# 09_-USB_IMU_GNSS.net
KiCad netlist of a schematic drawn in Altium Designer
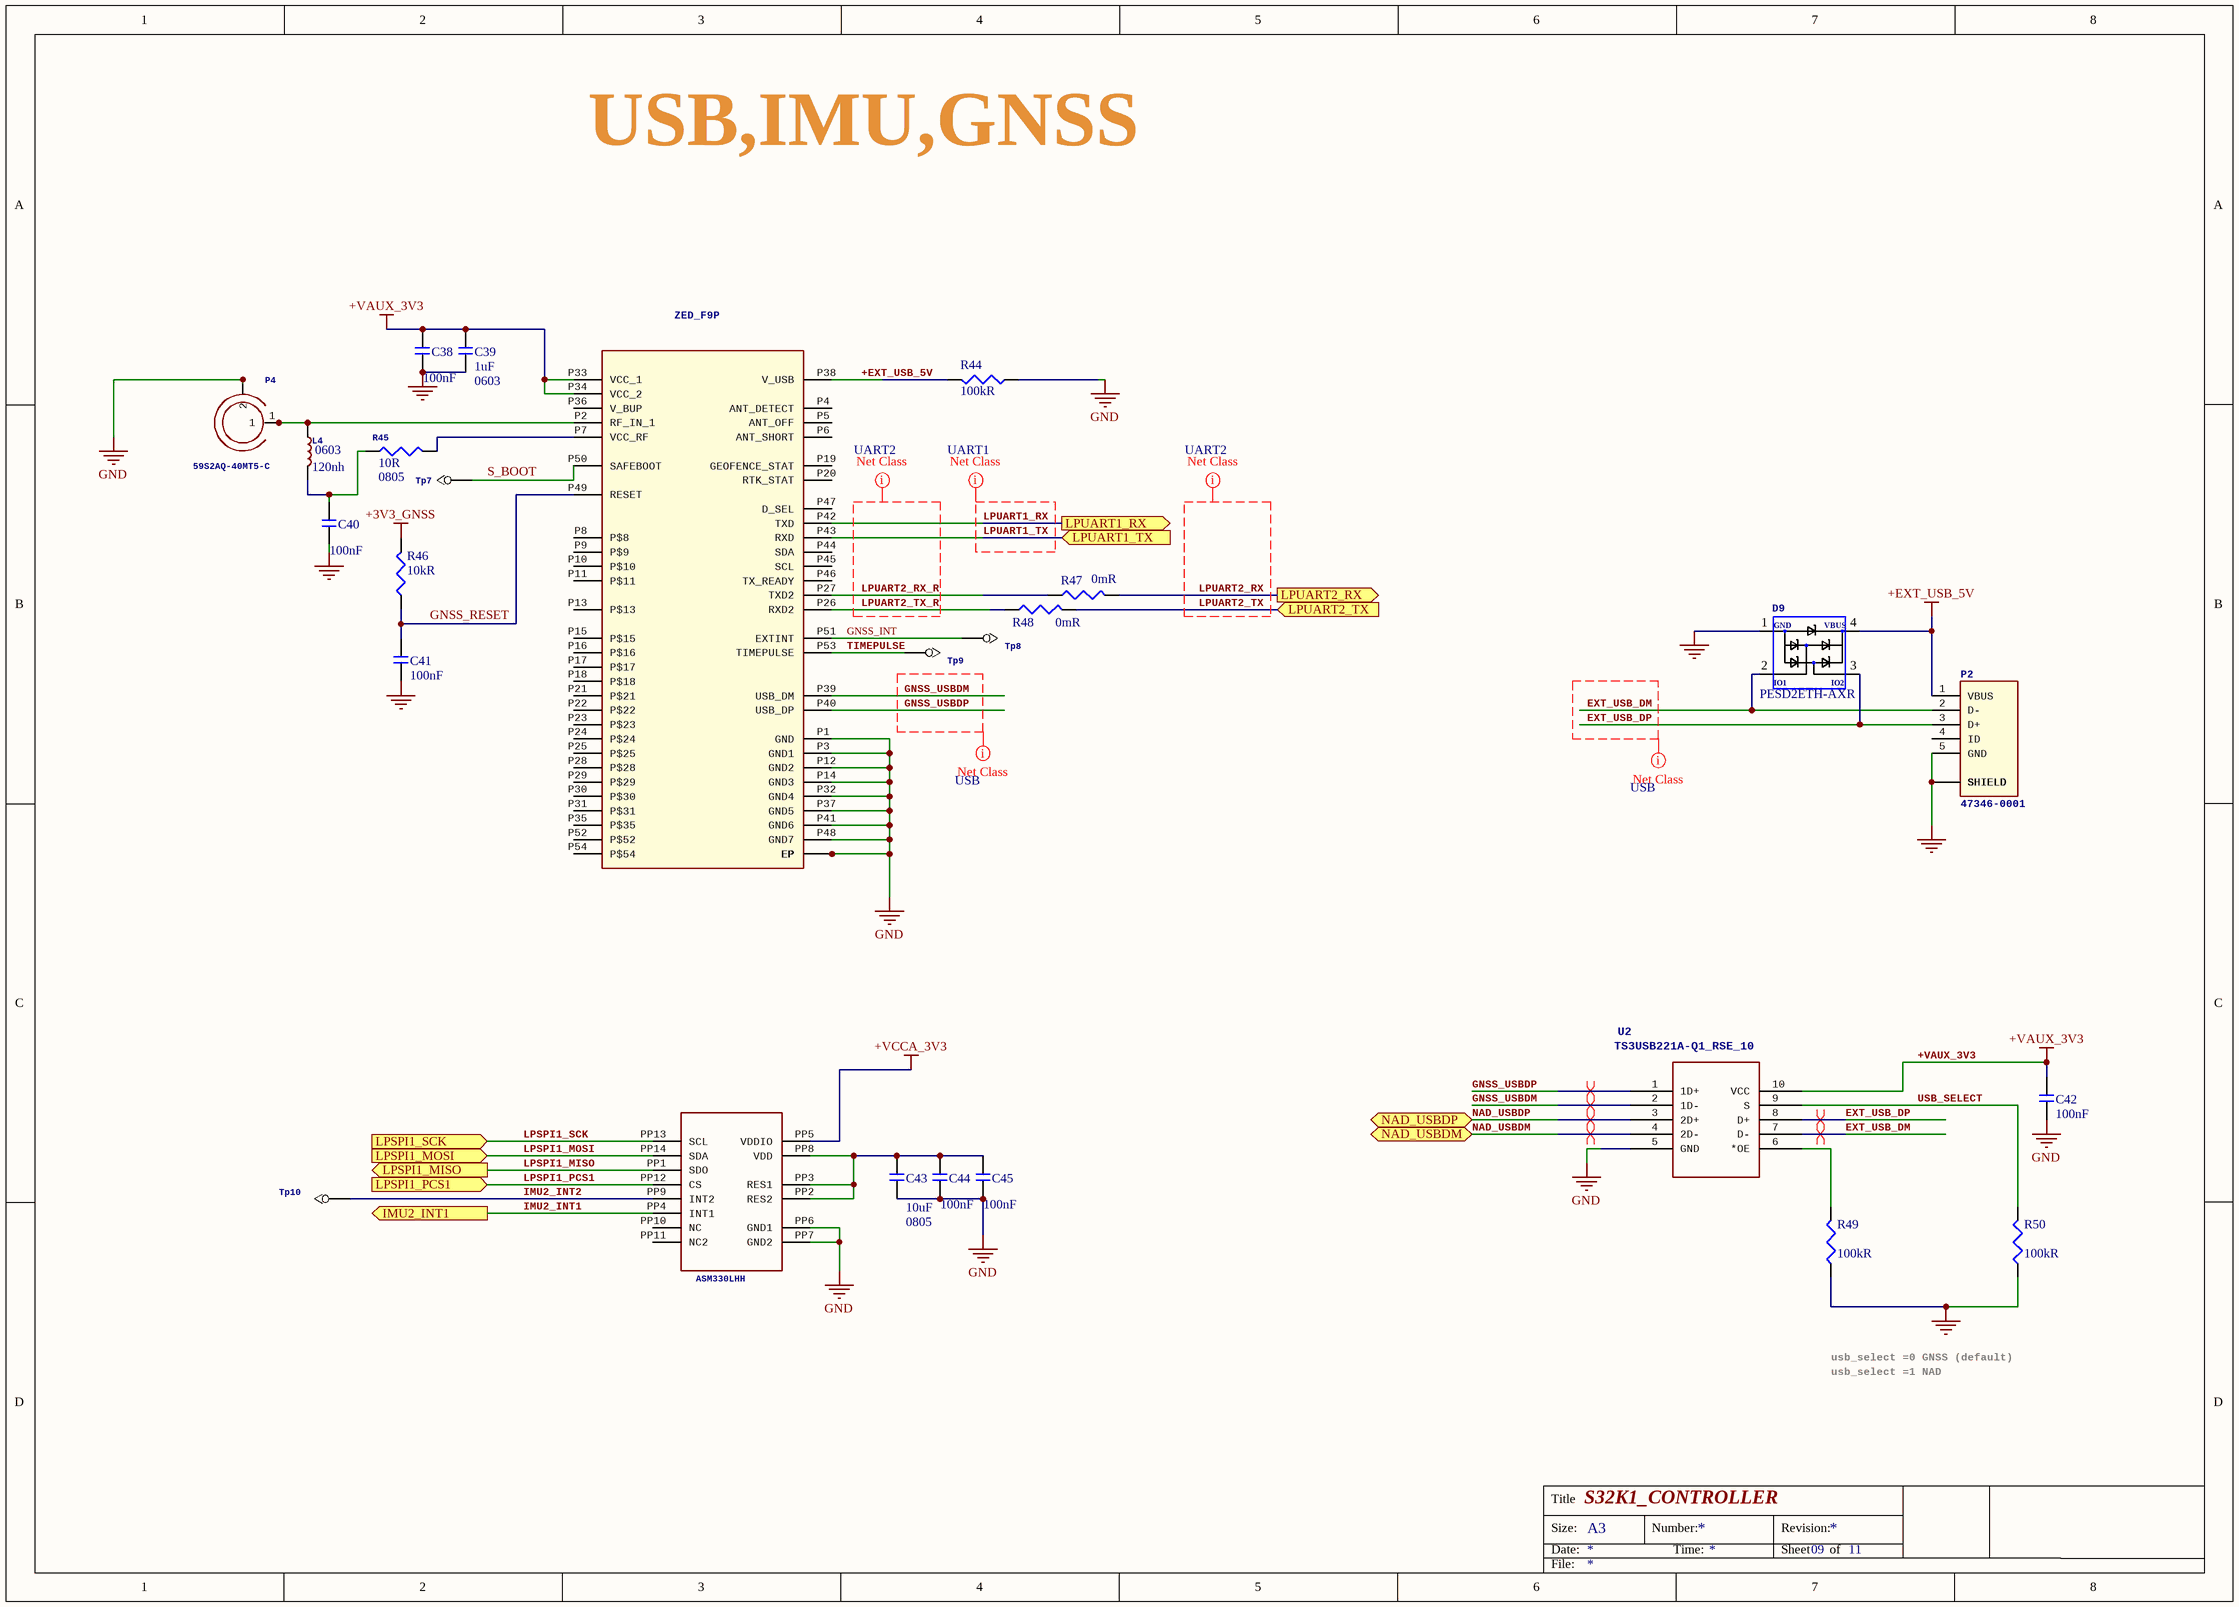
[diagram p0: [09]-USB,IMU,GNSS.SchDoc]

(export (version "E")
  (design (tool "Eeschema 10.0.6"))
  (components
    (comp (ref "C38")
      (value "GCM155R71C104KA55D")
      (footprint "CAP0402")
      (description "Multilayer Ceramic Capacitors (MLCC) - SMD/SMT 0402 0.1uF 16volts X7R 10%")
      (fields
        (field (name "MANUFACTURER") "Murata")
        (field (name "TOLERANCE") "10%")
        (field (name "CAPACITANCE") "100nF")
      )
      (libsource (lib "altium-import") (part "root_0_GCM155R71C104KA55D_"))
    )
    (comp (ref "C39")
      (value "CGA3E1X7R1C105K080AC")
      (footprint "CAP0603")
      (description "CGA Series 0603 1 uF 16 V ±10 % Tolerance X7R SMT Multilayer Ceramic Capacitor")
      (fields
        (field (name "MANUFACTURER") "TDK")
        (field (name "TOLERANCE") "10%")
        (field (name "CAPACITANCE") "1uF")
        (field (name "CASE/PACKAGE") "0603")
      )
      (libsource (lib "altium-import") (part "root_0_CGA3E1X7R1C105K080AC_"))
    )
    (comp (ref "C40")
      (value "GCM155R71C104KA55D")
      (footprint "CAP0402")
      (description "Multilayer Ceramic Capacitors (MLCC) - SMD/SMT 0402 0.1uF 16volts X7R 10%")
      (fields
        (field (name "MANUFACTURER") "Murata")
        (field (name "TOLERANCE") "10%")
        (field (name "CAPACITANCE") "100nF")
      )
      (libsource (lib "altium-import") (part "root_0_GCM155R71C104KA55D_"))
    )
    (comp (ref "C41")
      (value "GCM155R71C104KA55D")
      (footprint "CAP0402")
      (description "Multilayer Ceramic Capacitors (MLCC) - SMD/SMT 0402 0.1uF 16volts X7R 10%")
      (fields
        (field (name "MANUFACTURER") "Murata")
        (field (name "TOLERANCE") "10%")
        (field (name "CAPACITANCE") "100nF")
      )
      (libsource (lib "altium-import") (part "root_2_GCM155R71C104KA55D_"))
    )
    (comp (ref "C42")
      (value "GCM155R71C104KA55D")
      (footprint "CAP0402")
      (description "Multilayer Ceramic Capacitors (MLCC) - SMD/SMT 0402 0.1uF 16volts X7R 10%")
      (fields
        (field (name "MANUFACTURER") "Murata")
        (field (name "TOLERANCE") "10%")
        (field (name "CAPACITANCE") "100nF")
      )
      (libsource (lib "altium-import") (part "root_2_GCM155R71C104KA55D_"))
    )
    (comp (ref "C43")
      (value "CGA4J1X5R1C106K125AC")
      (footprint "CAP0805")
      (description "CGA Series 0805 10 uF 16 V ±10 % Tolerance X5R SMT Multilayer Ceramic Capacitor")
      (fields
        (field (name "MANUFACTURER") "TDK")
        (field (name "TOLERANCE") "10%")
        (field (name "CAPACITANCE") "10uF")
        (field (name "CASE/PACKAGE") "0805")
      )
      (libsource (lib "altium-import") (part "root_0_CGA4J1X5R1C106K125AC_"))
    )
    (comp (ref "C44")
      (value "GCM155R71C104KA55D")
      (footprint "CAP0402")
      (description "Multilayer Ceramic Capacitors (MLCC) - SMD/SMT 0402 0.1uF 16volts X7R 10%")
      (fields
        (field (name "MANUFACTURER") "Murata")
        (field (name "TOLERANCE") "10%")
        (field (name "CAPACITANCE") "100nF")
      )
      (libsource (lib "altium-import") (part "root_0_GCM155R71C104KA55D_"))
    )
    (comp (ref "C45")
      (value "GCM155R71C104KA55D")
      (footprint "CAP0402")
      (description "Multilayer Ceramic Capacitors (MLCC) - SMD/SMT 0402 0.1uF 16volts X7R 10%")
      (fields
        (field (name "MANUFACTURER") "Murata")
        (field (name "TOLERANCE") "10%")
        (field (name "CAPACITANCE") "100nF")
      )
      (libsource (lib "altium-import") (part "root_0_GCM155R71C104KA55D_"))
    )
    (comp (ref "D9")
      (value "PESD2ETH-AXR")
      (footprint "WEON_SOT192P238X100-4N")
      (description "PESD2ETH-AX - Ultra low capacitance double rail-to-rail ESD protection diode")
      (fields
        (field (name "MANUFACTURER") "NXP Semiconductors")
        (field (name "MANUFACTURER PART NUMBER") "PESD2ETH-AXR")
      )
      (libsource (lib "WeOnReferenceBoard") (part "PESD2ETH-AXR"))
    )
    (comp (ref "L4")
      (value "LQW18ANR12J00D")
      (footprint "RES0603")
      (description "Inductor RF Chip Wirewound 120nH 5% 100MHz 32Q-Factor 180mA 1.3Ohm DCR 0603 Paper T/R")
      (fields
        (field (name "MANUFACTURER") "Murata")
        (field (name "TOLERANCE") "5%")
        (field (name "CASE/PACKAGE") "0603")
        (field (name "INDUCTANCE") "120nh")
      )
      (libsource (lib "altium-import") (part "root_3_LQW18ANR12J00D_"))
    )
    (comp (ref "P2")
      (value "47346-0001")
      (footprint "MOLEX_47346-0001")
      (description "CONN RCPT 5POS MICRO USB R/A  SMD")
      (fields (field (name "MF") "Molex"))
      (libsource (lib "WeOnReferenceBoard") (part "47346-0001"))
    )
    (comp (ref "P4")
      (value "59S2AQ-40MT5-C")
      (footprint "59S2AQ-40MT5-C")
      (libsource (lib "WeOnReferenceBoard") (part "59S2AQ-40MT5-C"))
    )
    (comp (ref "R44")
      (value "ERJ-2GEJ104X")
      (footprint "RES0402")
      (description "Res Thick Film 0402 100K Ohm 5% 1/10W ±200ppm/°C Molded SMD SMD Punched Carrier T/R")
      (fields
        (field (name "MANUFACTURER") "Panasonic")
        (field (name "TOLERANCE") "5%")
        (field (name "RESISTANCE") "100kR")
      )
      (libsource (lib "WeOnReferenceBoard") (part "ERJ-2GEJ104X"))
    )
    (comp (ref "R45")
      (value "ERJ-6ENF10R0V")
      (footprint "RES0805")
      (description "Res Thick Film 0805 10 Ohm 1% 1/8W 灞100ppm/濉C Molded SMD SMD Punched Carrier")
      (fields
        (field (name "MANUFACTURER") "Panasonic")
        (field (name "TOLERANCE") "1%")
        (field (name "RESISTANCE") "10R")
        (field (name "CASE CODE (IMPERIAL)") "0805")
      )
      (libsource (lib "altium-import") (part "root_0_ERJ-6ENF10R0V_"))
    )
    (comp (ref "R46")
      (value "ERJ-2GEJ103X")
      (footprint "RES0402")
      (description "Res Thick Film 0402 10K Ohm 5% 1/10W ±200ppm/°C Molded SMD SMD Punched Carrier T/R")
      (fields
        (field (name "MANUFACTURER") "Panasonic")
        (field (name "TOLERANCE") "5%")
        (field (name "RESISTANCE") "10kR")
      )
      (libsource (lib "WeOnReferenceBoard") (part "ERJ-2GEJ103X"))
    )
    (comp (ref "R47")
      (value "ERJ-2GE0R00X")
      (footprint "RES0402")
      (description "ERJ Series 0402 0 Ohm 0.1 W Jumper Surface Mount Thick Film Chip Resistor")
      (fields
        (field (name "MANUFACTURER") "Panasonic")
        (field (name "TOLERANCE") "5%")
        (field (name "RESISTANCE") "0mR")
      )
      (libsource (lib "WeOnReferenceBoard") (part "ERJ-2GE0R00X"))
    )
    (comp (ref "R48")
      (value "ERJ-2GE0R00X")
      (footprint "RES0402")
      (description "ERJ Series 0402 0 Ohm 0.1 W Jumper Surface Mount Thick Film Chip Resistor")
      (fields
        (field (name "MANUFACTURER") "Panasonic")
        (field (name "TOLERANCE") "5%")
        (field (name "RESISTANCE") "0mR")
      )
      (libsource (lib "WeOnReferenceBoard") (part "ERJ-2GE0R00X"))
    )
    (comp (ref "R49")
      (value "ERJ-2GEJ104X")
      (footprint "RES0402")
      (description "Res Thick Film 0402 100K Ohm 5% 1/10W ±200ppm/°C Molded SMD SMD Punched Carrier T/R")
      (fields
        (field (name "MANUFACTURER") "Panasonic")
        (field (name "TOLERANCE") "5%")
        (field (name "RESISTANCE") "100kR")
      )
      (libsource (lib "WeOnReferenceBoard") (part "ERJ-2GEJ104X"))
    )
    (comp (ref "R50")
      (value "ERJ-2GEJ104X")
      (footprint "RES0402")
      (description "Res Thick Film 0402 100K Ohm 5% 1/10W ±200ppm/°C Molded SMD SMD Punched Carrier T/R")
      (fields
        (field (name "MANUFACTURER") "Panasonic")
        (field (name "TOLERANCE") "5%")
        (field (name "RESISTANCE") "100kR")
      )
      (libsource (lib "WeOnReferenceBoard") (part "ERJ-2GEJ104X"))
    )
    (comp (ref "ST")
      (value "ASM330LHH")
      (footprint "LGA2.5X3")
      (fields (field (name "ASM330LHH") "ASM330LHH"))
      (libsource (lib "WeOn") (part "ASM330LHH"))
    )
    (comp (ref "Tp7")
      (value "TP")
      (footprint "TestPoint")
      (libsource (lib "altium-import") (part "root_2_TP_"))
    )
    (comp (ref "Tp8")
      (value "TP")
      (footprint "TestPoint")
      (libsource (lib "altium-import") (part "root_0_TP_"))
    )
    (comp (ref "Tp9")
      (value "TP")
      (footprint "TestPoint")
      (libsource (lib "altium-import") (part "root_0_TP_"))
    )
    (comp (ref "Tp10")
      (value "TP")
      (footprint "TestPoint")
      (libsource (lib "altium-import") (part "root_2_TP_"))
    )
    (comp (ref "U$7")
      (value "GPS_UBLOX_ZED_F9P")
      (footprint "WEONREFERENCEBOARD_GPS_ZED")
      (fields (field (name "ZED_F9P") "ZED_F9P"))
      (libsource (lib "WeOnReferenceBoard") (part "GPS_UBLOX_ZED_F9P"))
    )
    (comp (ref "U2")
      (value "TS3USB221A-Q1_RSE_10")
      (footprint "WEONREFERENCEPLATFORM_RSE10")
      (fields
        (field (name "GENERIC_PART_NUMBER") "TS3USB221AQ1")
        (field (name "MANUFACTURER") "Texas Instruments")
        (field (name "MANUFACTURER_PART_NUMBER") "ts3usb221aq1_rse_10")
      )
      (libsource (lib "WeOnReferenceBoard") (part "TS3USB221A-Q1_RSE_10"))
    )
  )
  (nets
    (net (code "1") (name "+3V3_GNSS") (class "Default")
      (node (ref "R46") (pin "2") (pinfunction "2_2") (pintype "passive"))
    )
    (net (code "2") (name "+EXT_USB_5V") (class "Default")
      (node (ref "D9") (pin "4") (pinfunction "4_4") (pintype "passive"))
      (node (ref "P2") (pin "1") (pinfunction "VBUS_1") (pintype "power_in"))
      (node (ref "R44") (pin "2") (pinfunction "2_2") (pintype "passive"))
      (node (ref "U$7") (pin "P38") (pinfunction "V_USB_P38") (pintype "passive"))
    )
    (net (code "3") (name "+VAUX_3V3") (class "Default")
      (node (ref "C38") (pin "1") (pinfunction "1_1") (pintype "passive"))
      (node (ref "C39") (pin "1") (pinfunction "1_1") (pintype "passive"))
      (node (ref "C42") (pin "2") (pinfunction "2_2") (pintype "passive"))
      (node (ref "U$7") (pin "P33") (pinfunction "VCC_1_P33") (pintype "passive"))
      (node (ref "U$7") (pin "P34") (pinfunction "VCC_2_P34") (pintype "passive"))
      (node (ref "U2") (pin "10") (pinfunction "VCC_10") (pintype "power_in"))
    )
    (net (code "4") (name "+VCCA_3V3") (class "Default")
      (node (ref "ST") (pin "PP5") (pinfunction "VDDIO_PP5") (pintype "passive"))
    )
    (net (code "5") (name "/EXT_USB_DM") (class "Default")
      (node (ref "D9") (pin "2") (pinfunction "2_2") (pintype "passive"))
      (node (ref "P2") (pin "2") (pinfunction "D-_2") (pintype "passive"))
      (node (ref "U2") (pin "7") (pinfunction "D-_7") (pintype "passive"))
    )
    (net (code "6") (name "/EXT_USB_DP") (class "Default")
      (node (ref "D9") (pin "3") (pinfunction "3_3") (pintype "passive"))
      (node (ref "P2") (pin "3") (pinfunction "D+_3") (pintype "passive"))
      (node (ref "U2") (pin "8") (pinfunction "D+_8") (pintype "passive"))
    )
    (net (code "7") (name "/GNSS_INT") (class "Default")
      (node (ref "Tp8") (pin "1") (pinfunction "1_1") (pintype "passive"))
      (node (ref "U$7") (pin "P51") (pinfunction "EXTINT_P51") (pintype "passive"))
    )
    (net (code "8") (name "/GNSS_RESET") (class "Default")
      (node (ref "C41") (pin "2") (pinfunction "2_2") (pintype "passive"))
      (node (ref "R46") (pin "1") (pinfunction "1_1") (pintype "passive"))
      (node (ref "U$7") (pin "P49") (pinfunction "RESET_P49") (pintype "passive"))
    )
    (net (code "9") (name "/GNSS_USBDM") (class "Default")
      (node (ref "U$7") (pin "P39") (pinfunction "USB_DM_P39") (pintype "passive"))
      (node (ref "U2") (pin "2") (pinfunction "1D-_2") (pintype "passive"))
    )
    (net (code "10") (name "/GNSS_USBDP") (class "Default")
      (node (ref "U$7") (pin "P40") (pinfunction "USB_DP_P40") (pintype "passive"))
      (node (ref "U2") (pin "1") (pinfunction "1D+_1") (pintype "passive"))
    )
    (net (code "11") (name "/IMU2_INT1") (class "Default")
      (node (ref "ST") (pin "PP4") (pinfunction "INT1_PP4") (pintype "passive"))
    )
    (net (code "12") (name "/IMU2_INT2") (class "Default")
      (node (ref "ST") (pin "PP9") (pinfunction "INT2_PP9") (pintype "passive"))
      (node (ref "Tp10") (pin "1") (pinfunction "1_1") (pintype "passive"))
    )
    (net (code "13") (name "/LPSPI1_MISO") (class "Default")
      (node (ref "ST") (pin "PP1") (pinfunction "SDO_PP1") (pintype "passive"))
    )
    (net (code "14") (name "/LPSPI1_MOSI") (class "Default")
      (node (ref "ST") (pin "PP14") (pinfunction "SDA_PP14") (pintype "passive"))
    )
    (net (code "15") (name "/LPSPI1_PCS1") (class "Default")
      (node (ref "ST") (pin "PP12") (pinfunction "CS_PP12") (pintype "passive"))
    )
    (net (code "16") (name "/LPSPI1_SCK") (class "Default")
      (node (ref "ST") (pin "PP13") (pinfunction "SCL_PP13") (pintype "passive"))
    )
    (net (code "17") (name "/LPUART1_RX") (class "Default")
      (node (ref "U$7") (pin "P42") (pinfunction "TXD_P42") (pintype "passive"))
    )
    (net (code "18") (name "/LPUART1_TX") (class "Default")
      (node (ref "U$7") (pin "P43") (pinfunction "RXD_P43") (pintype "passive"))
    )
    (net (code "19") (name "/LPUART2_RX") (class "Default")
      (node (ref "R47") (pin "2") (pinfunction "2_2") (pintype "passive"))
    )
    (net (code "20") (name "/LPUART2_RX_R") (class "Default")
      (node (ref "R47") (pin "1") (pinfunction "1_1") (pintype "passive"))
      (node (ref "U$7") (pin "P27") (pinfunction "TXD2_P27") (pintype "passive"))
    )
    (net (code "21") (name "/LPUART2_TX") (class "Default")
      (node (ref "R48") (pin "2") (pinfunction "2_2") (pintype "passive"))
    )
    (net (code "22") (name "/LPUART2_TX_R") (class "Default")
      (node (ref "R48") (pin "1") (pinfunction "1_1") (pintype "passive"))
      (node (ref "U$7") (pin "P26") (pinfunction "RXD2_P26") (pintype "passive"))
    )
    (net (code "23") (name "/NAD_USBDM") (class "Default")
      (node (ref "U2") (pin "4") (pinfunction "2D-_4") (pintype "passive"))
    )
    (net (code "24") (name "/NAD_USBDP") (class "Default")
      (node (ref "U2") (pin "3") (pinfunction "2D+_3") (pintype "passive"))
    )
    (net (code "25") (name "/S_BOOT") (class "Default")
      (node (ref "Tp7") (pin "1") (pinfunction "1_1") (pintype "passive"))
      (node (ref "U$7") (pin "P50") (pinfunction "SAFEBOOT_P50") (pintype "passive"))
    )
    (net (code "26") (name "/TIMEPULSE") (class "Default")
      (node (ref "Tp9") (pin "1") (pinfunction "1_1") (pintype "passive"))
      (node (ref "U$7") (pin "P53") (pinfunction "TIMEPULSE_P53") (pintype "passive"))
    )
    (net (code "27") (name "/USB_SELECT") (class "Default")
      (node (ref "R50") (pin "2") (pinfunction "2_2") (pintype "passive"))
      (node (ref "U2") (pin "9") (pinfunction "S_9") (pintype "passive"))
    )
    (net (code "28") (name "GND") (class "Default")
      (node (ref "C38") (pin "2") (pinfunction "2_2") (pintype "passive"))
      (node (ref "C39") (pin "2") (pinfunction "2_2") (pintype "passive"))
      (node (ref "C40") (pin "2") (pinfunction "2_2") (pintype "passive"))
      (node (ref "C41") (pin "1") (pinfunction "1_1") (pintype "passive"))
      (node (ref "C42") (pin "1") (pinfunction "1_1") (pintype "passive"))
      (node (ref "C43") (pin "2") (pinfunction "2_2") (pintype "passive"))
      (node (ref "C44") (pin "2") (pinfunction "2_2") (pintype "passive"))
      (node (ref "C45") (pin "2") (pinfunction "2_2") (pintype "passive"))
      (node (ref "D9") (pin "1") (pinfunction "1_1") (pintype "passive"))
      (node (ref "P2") (pin "5") (pinfunction "GND_5") (pintype "power_in"))
      (node (ref "P2") (pin "SH1") (pinfunction "SHIELD_SH1") (pintype "passive"))
      (node (ref "P2") (pin "SH2") (pinfunction "SHIELD_SH2") (pintype "passive"))
      (node (ref "P2") (pin "SH3") (pinfunction "SHIELD_SH3") (pintype "passive"))
      (node (ref "P2") (pin "SH4") (pinfunction "SHIELD_SH4") (pintype "passive"))
      (node (ref "P2") (pin "SH5") (pinfunction "SHIELD_SH5") (pintype "passive"))
      (node (ref "P2") (pin "SH6") (pinfunction "SHIELD_SH6") (pintype "passive"))
      (node (ref "P4") (pin "2_3_4_5_6_7_8_9") (pinfunction "2_2_3_4_5_6_7_8_9") (pintype "passive"))
      (node (ref "P4") (pin "3") (pinfunction "3_3") (pintype "passive"))
      (node (ref "P4") (pin "4") (pinfunction "4_4") (pintype "passive"))
      (node (ref "P4") (pin "5") (pinfunction "5_5") (pintype "passive"))
      (node (ref "P4") (pin "6") (pinfunction "6_6") (pintype "passive"))
      (node (ref "P4") (pin "7") (pinfunction "7_7") (pintype "passive"))
      (node (ref "P4") (pin "8") (pinfunction "8_8") (pintype "passive"))
      (node (ref "R44") (pin "1") (pinfunction "1_1") (pintype "passive"))
      (node (ref "R49") (pin "1") (pinfunction "1_1") (pintype "passive"))
      (node (ref "R50") (pin "1") (pinfunction "1_1") (pintype "passive"))
      (node (ref "ST") (pin "PP6") (pinfunction "GND1_PP6") (pintype "passive"))
      (node (ref "ST") (pin "PP7") (pinfunction "GND2_PP7") (pintype "passive"))
      (node (ref "U$7") (pin "100") (pinfunction "EP_100") (pintype "passive"))
      (node (ref "U$7") (pin "101") (pinfunction "EP_101") (pintype "passive"))
      (node (ref "U$7") (pin "102") (pinfunction "EP_102") (pintype "passive"))
      (node (ref "U$7") (pin "55") (pinfunction "EP_55") (pintype "passive"))
      (node (ref "U$7") (pin "55_56_57_58_59_60_61_62_63_64_65_66_67_68_69_70_71_72_73_74_75_76_77_78_79_80_81_82_83_84_85_86_87_88_89_90_91_92_93_94_95_96_97_98_99_100_101_102") (pinfunction "EP_55_56_57_58_59_60_61_62_63_64_65_66_67_68_69_70_71_72_73_74_75_76_77_78_79_80_81_82_83_84_85_86_87_88_89_90_91_92_93_94_95_96_97_98_99_100_101_102") (pintype "passive"))
      (node (ref "U$7") (pin "56") (pinfunction "EP_56") (pintype "passive"))
      (node (ref "U$7") (pin "57") (pinfunction "EP_57") (pintype "passive"))
      (node (ref "U$7") (pin "58") (pinfunction "EP_58") (pintype "passive"))
      (node (ref "U$7") (pin "59") (pinfunction "EP_59") (pintype "passive"))
      (node (ref "U$7") (pin "60") (pinfunction "EP_60") (pintype "passive"))
      (node (ref "U$7") (pin "61") (pinfunction "EP_61") (pintype "passive"))
      (node (ref "U$7") (pin "62") (pinfunction "EP_62") (pintype "passive"))
      (node (ref "U$7") (pin "63") (pinfunction "EP_63") (pintype "passive"))
      (node (ref "U$7") (pin "64") (pinfunction "EP_64") (pintype "passive"))
      (node (ref "U$7") (pin "65") (pinfunction "EP_65") (pintype "passive"))
      (node (ref "U$7") (pin "66") (pinfunction "EP_66") (pintype "passive"))
      (node (ref "U$7") (pin "67") (pinfunction "EP_67") (pintype "passive"))
      (node (ref "U$7") (pin "68") (pinfunction "EP_68") (pintype "passive"))
      (node (ref "U$7") (pin "69") (pinfunction "EP_69") (pintype "passive"))
      (node (ref "U$7") (pin "70") (pinfunction "EP_70") (pintype "passive"))
      (node (ref "U$7") (pin "71") (pinfunction "EP_71") (pintype "passive"))
      (node (ref "U$7") (pin "72") (pinfunction "EP_72") (pintype "passive"))
      (node (ref "U$7") (pin "73") (pinfunction "EP_73") (pintype "passive"))
      (node (ref "U$7") (pin "74") (pinfunction "EP_74") (pintype "passive"))
      (node (ref "U$7") (pin "75") (pinfunction "EP_75") (pintype "passive"))
      (node (ref "U$7") (pin "76") (pinfunction "EP_76") (pintype "passive"))
      (node (ref "U$7") (pin "77") (pinfunction "EP_77") (pintype "passive"))
      (node (ref "U$7") (pin "78") (pinfunction "EP_78") (pintype "passive"))
      (node (ref "U$7") (pin "79") (pinfunction "EP_79") (pintype "passive"))
      (node (ref "U$7") (pin "80") (pinfunction "EP_80") (pintype "passive"))
      (node (ref "U$7") (pin "81") (pinfunction "EP_81") (pintype "passive"))
      (node (ref "U$7") (pin "82") (pinfunction "EP_82") (pintype "passive"))
      (node (ref "U$7") (pin "83") (pinfunction "EP_83") (pintype "passive"))
      (node (ref "U$7") (pin "84") (pinfunction "EP_84") (pintype "passive"))
      (node (ref "U$7") (pin "85") (pinfunction "EP_85") (pintype "passive"))
      (node (ref "U$7") (pin "86") (pinfunction "EP_86") (pintype "passive"))
      (node (ref "U$7") (pin "87") (pinfunction "EP_87") (pintype "passive"))
      (node (ref "U$7") (pin "88") (pinfunction "EP_88") (pintype "passive"))
      (node (ref "U$7") (pin "89") (pinfunction "EP_89") (pintype "passive"))
      (node (ref "U$7") (pin "90") (pinfunction "EP_90") (pintype "passive"))
      (node (ref "U$7") (pin "91") (pinfunction "EP_91") (pintype "passive"))
      (node (ref "U$7") (pin "92") (pinfunction "EP_92") (pintype "passive"))
      (node (ref "U$7") (pin "93") (pinfunction "EP_93") (pintype "passive"))
      (node (ref "U$7") (pin "94") (pinfunction "EP_94") (pintype "passive"))
      (node (ref "U$7") (pin "95") (pinfunction "EP_95") (pintype "passive"))
      (node (ref "U$7") (pin "96") (pinfunction "EP_96") (pintype "passive"))
      (node (ref "U$7") (pin "97") (pinfunction "EP_97") (pintype "passive"))
      (node (ref "U$7") (pin "98") (pinfunction "EP_98") (pintype "passive"))
      (node (ref "U$7") (pin "99") (pinfunction "EP_99") (pintype "passive"))
      (node (ref "U$7") (pin "P1") (pinfunction "GND_P1") (pintype "passive"))
      (node (ref "U$7") (pin "P12") (pinfunction "GND2_P12") (pintype "passive"))
      (node (ref "U$7") (pin "P14") (pinfunction "GND3_P14") (pintype "passive"))
      (node (ref "U$7") (pin "P3") (pinfunction "GND1_P3") (pintype "passive"))
      (node (ref "U$7") (pin "P32") (pinfunction "GND4_P32") (pintype "passive"))
      (node (ref "U$7") (pin "P37") (pinfunction "GND5_P37") (pintype "passive"))
      (node (ref "U$7") (pin "P41") (pinfunction "GND6_P41") (pintype "passive"))
      (node (ref "U$7") (pin "P48") (pinfunction "GND7_P48") (pintype "passive"))
      (node (ref "U2") (pin "5") (pinfunction "GND_5") (pintype "power_in"))
    )
    (net (code "29") (name "Net-(C40-Pad1)") (class "Default")
      (node (ref "C40") (pin "1") (pinfunction "1_1") (pintype "passive"))
      (node (ref "L4") (pin "2") (pinfunction "2_2") (pintype "passive"))
      (node (ref "R45") (pin "1") (pinfunction "1_1") (pintype "passive"))
    )
    (net (code "30") (name "Net-(ST-RES1)") (class "Default")
      (node (ref "C43") (pin "1") (pinfunction "1_1") (pintype "passive"))
      (node (ref "C44") (pin "1") (pinfunction "1_1") (pintype "passive"))
      (node (ref "C45") (pin "1") (pinfunction "1_1") (pintype "passive"))
      (node (ref "ST") (pin "PP2") (pinfunction "RES2_PP2") (pintype "passive"))
      (node (ref "ST") (pin "PP3") (pinfunction "RES1_PP3") (pintype "passive"))
      (node (ref "ST") (pin "PP8") (pinfunction "VDD_PP8") (pintype "passive"))
    )
    (net (code "31") (name "Net-(U$7-RF_IN_1)") (class "Default")
      (node (ref "L4") (pin "1") (pinfunction "1_1") (pintype "passive"))
      (node (ref "P4") (pin "1") (pinfunction "1_1") (pintype "passive"))
      (node (ref "U$7") (pin "P2") (pinfunction "RF_IN_1_P2") (pintype "passive"))
    )
    (net (code "32") (name "Net-(U$7-VCC_RF)") (class "Default")
      (node (ref "R45") (pin "2") (pinfunction "2_2") (pintype "passive"))
      (node (ref "U$7") (pin "P7") (pinfunction "VCC_RF_P7") (pintype "passive"))
    )
    (net (code "33") (name "Net-(U2-*OE)") (class "Default")
      (node (ref "R49") (pin "2") (pinfunction "2_2") (pintype "passive"))
      (node (ref "U2") (pin "6") (pinfunction "*OE_6") (pintype "passive"))
    )
    (net (code "34") (name "unconnected-(P2-ID-Pad4)") (class "Default")
      (node (ref "P2") (pin "4") (pinfunction "ID_4") (pintype "passive"))
    )
    (net (code "35") (name "unconnected-(ST-NC-PadPP10)") (class "Default")
      (node (ref "ST") (pin "PP10") (pinfunction "NC_PP10") (pintype "passive"))
    )
    (net (code "36") (name "unconnected-(ST-NC2-PadPP11)") (class "Default")
      (node (ref "ST") (pin "PP11") (pinfunction "NC2_PP11") (pintype "passive"))
    )
    (net (code "37") (name "unconnected-(U$7-ANT_DETECT-PadP4)") (class "Default")
      (node (ref "U$7") (pin "P4") (pinfunction "ANT_DETECT_P4") (pintype "passive"))
    )
    (net (code "38") (name "unconnected-(U$7-ANT_OFF-PadP5)") (class "Default")
      (node (ref "U$7") (pin "P5") (pinfunction "ANT_OFF_P5") (pintype "passive"))
    )
    (net (code "39") (name "unconnected-(U$7-ANT_SHORT-PadP6)") (class "Default")
      (node (ref "U$7") (pin "P6") (pinfunction "ANT_SHORT_P6") (pintype "passive"))
    )
    (net (code "40") (name "unconnected-(U$7-D_SEL-PadP47)") (class "Default")
      (node (ref "U$7") (pin "P47") (pinfunction "D_SEL_P47") (pintype "passive"))
    )
    (net (code "41") (name "unconnected-(U$7-GEOFENCE_STAT-PadP19)") (class "Default")
      (node (ref "U$7") (pin "P19") (pinfunction "GEOFENCE_STAT_P19") (pintype "passive"))
    )
    (net (code "42") (name "unconnected-(U$7-P$8-PadP8)") (class "Default")
      (node (ref "U$7") (pin "P8") (pinfunction "P$8_P8") (pintype "passive"))
    )
    (net (code "43") (name "unconnected-(U$7-P$9-PadP9)") (class "Default")
      (node (ref "U$7") (pin "P9") (pinfunction "P$9_P9") (pintype "passive"))
    )
    (net (code "44") (name "unconnected-(U$7-P$10-PadP10)") (class "Default")
      (node (ref "U$7") (pin "P10") (pinfunction "P$10_P10") (pintype "passive"))
    )
    (net (code "45") (name "unconnected-(U$7-P$11-PadP11)") (class "Default")
      (node (ref "U$7") (pin "P11") (pinfunction "P$11_P11") (pintype "passive"))
    )
    (net (code "46") (name "unconnected-(U$7-P$13-PadP13)") (class "Default")
      (node (ref "U$7") (pin "P13") (pinfunction "P$13_P13") (pintype "passive"))
    )
    (net (code "47") (name "unconnected-(U$7-P$15-PadP15)") (class "Default")
      (node (ref "U$7") (pin "P15") (pinfunction "P$15_P15") (pintype "passive"))
    )
    (net (code "48") (name "unconnected-(U$7-P$16-PadP16)") (class "Default")
      (node (ref "U$7") (pin "P16") (pinfunction "P$16_P16") (pintype "passive"))
    )
    (net (code "49") (name "unconnected-(U$7-P$17-PadP17)") (class "Default")
      (node (ref "U$7") (pin "P17") (pinfunction "P$17_P17") (pintype "passive"))
    )
    (net (code "50") (name "unconnected-(U$7-P$18-PadP18)") (class "Default")
      (node (ref "U$7") (pin "P18") (pinfunction "P$18_P18") (pintype "passive"))
    )
    (net (code "51") (name "unconnected-(U$7-P$21-PadP21)") (class "Default")
      (node (ref "U$7") (pin "P21") (pinfunction "P$21_P21") (pintype "passive"))
    )
    (net (code "52") (name "unconnected-(U$7-P$22-PadP22)") (class "Default")
      (node (ref "U$7") (pin "P22") (pinfunction "P$22_P22") (pintype "passive"))
    )
    (net (code "53") (name "unconnected-(U$7-P$23-PadP23)") (class "Default")
      (node (ref "U$7") (pin "P23") (pinfunction "P$23_P23") (pintype "passive"))
    )
    (net (code "54") (name "unconnected-(U$7-P$24-PadP24)") (class "Default")
      (node (ref "U$7") (pin "P24") (pinfunction "P$24_P24") (pintype "passive"))
    )
    (net (code "55") (name "unconnected-(U$7-P$25-PadP25)") (class "Default")
      (node (ref "U$7") (pin "P25") (pinfunction "P$25_P25") (pintype "passive"))
    )
    (net (code "56") (name "unconnected-(U$7-P$28-PadP28)") (class "Default")
      (node (ref "U$7") (pin "P28") (pinfunction "P$28_P28") (pintype "passive"))
    )
    (net (code "57") (name "unconnected-(U$7-P$29-PadP29)") (class "Default")
      (node (ref "U$7") (pin "P29") (pinfunction "P$29_P29") (pintype "passive"))
    )
    (net (code "58") (name "unconnected-(U$7-P$30-PadP30)") (class "Default")
      (node (ref "U$7") (pin "P30") (pinfunction "P$30_P30") (pintype "passive"))
    )
    (net (code "59") (name "unconnected-(U$7-P$31-PadP31)") (class "Default")
      (node (ref "U$7") (pin "P31") (pinfunction "P$31_P31") (pintype "passive"))
    )
    (net (code "60") (name "unconnected-(U$7-P$35-PadP35)") (class "Default")
      (node (ref "U$7") (pin "P35") (pinfunction "P$35_P35") (pintype "passive"))
    )
    (net (code "61") (name "unconnected-(U$7-P$52-PadP52)") (class "Default")
      (node (ref "U$7") (pin "P52") (pinfunction "P$52_P52") (pintype "passive"))
    )
    (net (code "62") (name "unconnected-(U$7-P$54-PadP54)") (class "Default")
      (node (ref "U$7") (pin "P54") (pinfunction "P$54_P54") (pintype "passive"))
    )
    (net (code "63") (name "unconnected-(U$7-RTK_STAT-PadP20)") (class "Default")
      (node (ref "U$7") (pin "P20") (pinfunction "RTK_STAT_P20") (pintype "passive"))
    )
    (net (code "64") (name "unconnected-(U$7-SCL-PadP45)") (class "Default")
      (node (ref "U$7") (pin "P45") (pinfunction "SCL_P45") (pintype "passive"))
    )
    (net (code "65") (name "unconnected-(U$7-SDA-PadP44)") (class "Default")
      (node (ref "U$7") (pin "P44") (pinfunction "SDA_P44") (pintype "passive"))
    )
    (net (code "66") (name "unconnected-(U$7-TX_READY-PadP46)") (class "Default")
      (node (ref "U$7") (pin "P46") (pinfunction "TX_READY_P46") (pintype "passive"))
    )
    (net (code "67") (name "unconnected-(U$7-V_BUP-PadP36)") (class "Default")
      (node (ref "U$7") (pin "P36") (pinfunction "V_BUP_P36") (pintype "passive"))
    )
  )
)
